# PDB_Schematic_v1_0.net
KiCad netlist of a schematic drawn in Altium Designer
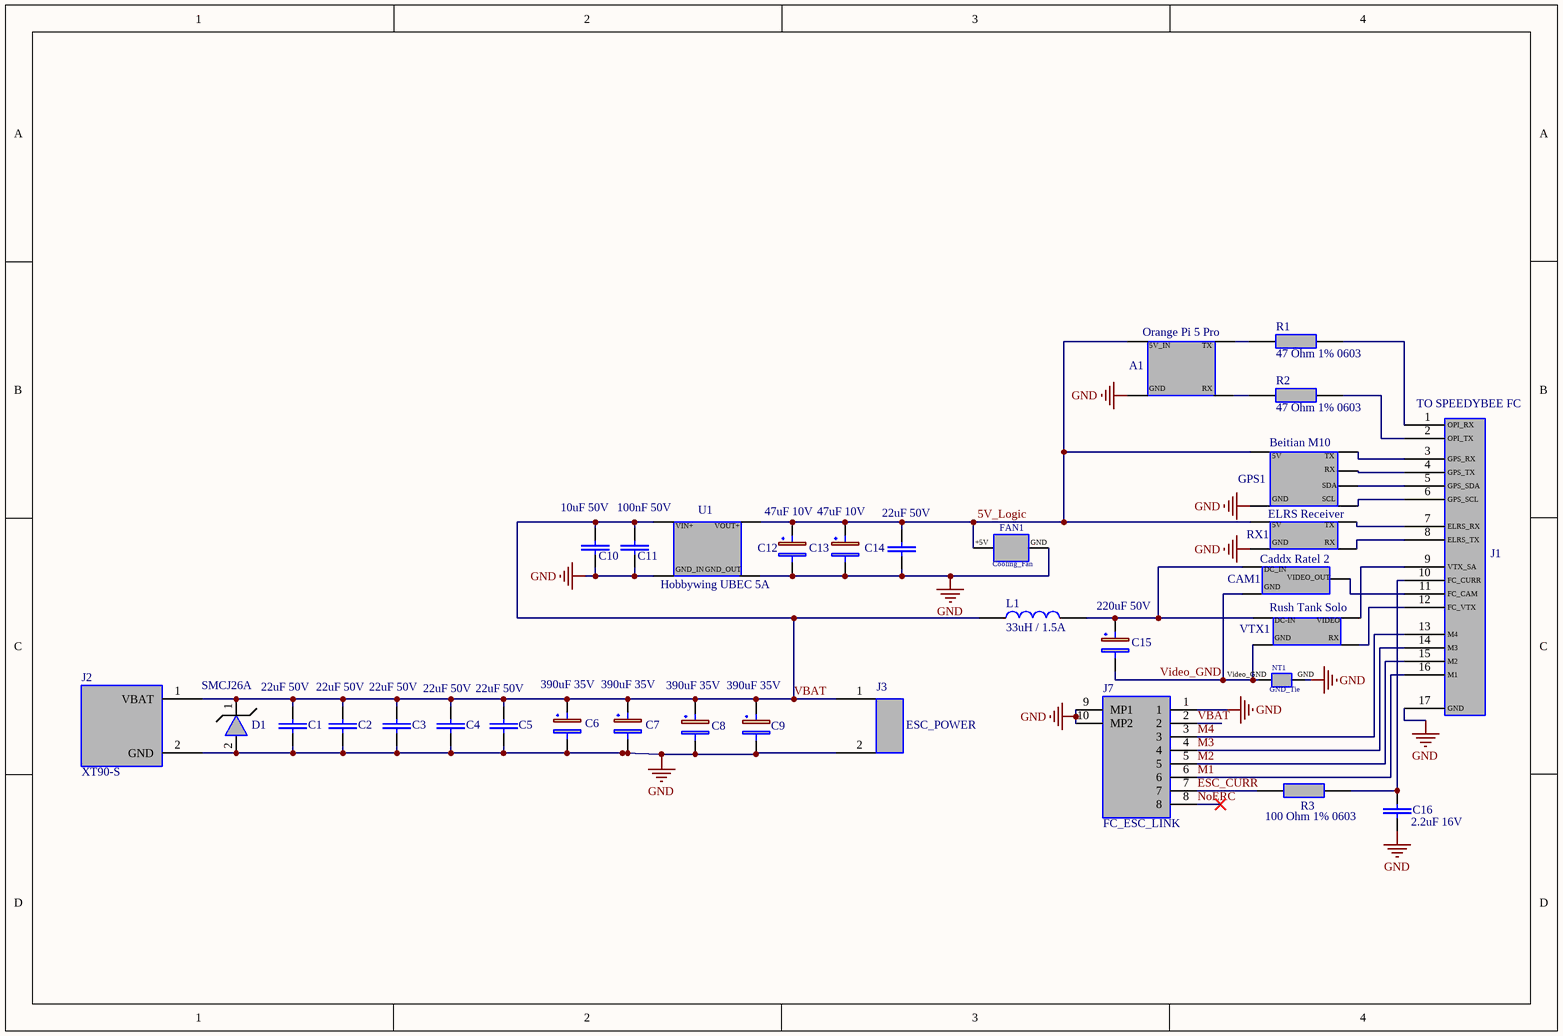
[diagram p0: PDB_Schematic_v1.0.SchDoc]

(export (version "E")
  (design (tool "Eeschema 10.0.6"))
  (components
    (comp (ref "A1")
      (value "Orange Pi 5 Pro")
      (footprint "PDB_Footprints_v1.0:FOOTPRINT_ORANGE_PI")
      (libsource (lib "PDB_Components_v1.0") (part "Orange Pi 5 Pro"))
    )
    (comp (ref "C1")
      (value "22uF 50V")
      (footprint "PDB_Footprints_v1.0:1210")
      (libsource (lib "PDB_Components_v1.0") (part "Cap_MLCC"))
    )
    (comp (ref "C2")
      (value "22uF 50V")
      (footprint "PDB_Footprints_v1.0:1210")
      (libsource (lib "PDB_Components_v1.0") (part "Cap_MLCC"))
    )
    (comp (ref "C3")
      (value "22uF 50V")
      (footprint "PDB_Footprints_v1.0:1210")
      (libsource (lib "PDB_Components_v1.0") (part "Cap_MLCC"))
    )
    (comp (ref "C4")
      (value "22uF 50V")
      (footprint "PDB_Footprints_v1.0:1210")
      (libsource (lib "PDB_Components_v1.0") (part "Cap_MLCC"))
    )
    (comp (ref "C5")
      (value "22uF 50V")
      (footprint "PDB_Footprints_v1.0:1210")
      (libsource (lib "PDB_Components_v1.0") (part "Cap_MLCC"))
    )
    (comp (ref "C6")
      (value "390uF 35V")
      (footprint "PDB_Footprints_v1.0:CAP_ELEC_D10.0_P5.0")
      (description "Low ESR Aluminum Electrolytic Capacitor, Panasonic FR Series, 390uF 35V, Radial, 5mm Lead Pitc")
      (fields (field (name "VOLTAGE") "35V") (field (name "MANUFACTURER") "Panasonic"))
      (libsource (lib "PDB_Components_v1.0") (part "Cap_Low_ESR"))
    )
    (comp (ref "C7")
      (value "390uF 35V")
      (footprint "PDB_Footprints_v1.0:CAP_ELEC_D10.0_P5.0")
      (description "Low ESR Aluminum Electrolytic Capacitor, Panasonic FR Series, 390uF 35V, Radial, 5mm Lead Pitc")
      (fields (field (name "VOLTAGE") "35V") (field (name "MANUFACTURER") "Panasonic"))
      (libsource (lib "PDB_Components_v1.0") (part "Cap_Low_ESR"))
    )
    (comp (ref "C8")
      (value "390uF 35V")
      (footprint "PDB_Footprints_v1.0:CAP_ELEC_D10.0_P5.0")
      (description "Low ESR Aluminum Electrolytic Capacitor, Panasonic FR Series, 390uF 35V, Radial, 5mm Lead Pitc")
      (fields (field (name "VOLTAGE") "35V") (field (name "MANUFACTURER") "Panasonic"))
      (libsource (lib "PDB_Components_v1.0") (part "Cap_Low_ESR"))
    )
    (comp (ref "C9")
      (value "390uF 35V")
      (footprint "PDB_Footprints_v1.0:CAP_ELEC_D10.0_P5.0")
      (description "Low ESR Aluminum Electrolytic Capacitor, Panasonic FR Series, 390uF 35V, Radial, 5mm Lead Pitc")
      (fields (field (name "VOLTAGE") "35V") (field (name "MANUFACTURER") "Panasonic"))
      (libsource (lib "PDB_Components_v1.0") (part "Cap_Low_ESR"))
    )
    (comp (ref "C10")
      (value "10uF 50V")
      (footprint "PDB_Footprints_v1.0:1206")
      (description "Ceramic Capacitor, 10 uF, 50 V, X7R Dielectric, 1206 SMD, UBEC VIN Buffer")
      (libsource (lib "PDB_Components_v1.0") (part "Cap_Cer_10uF_50V_1206"))
    )
    (comp (ref "C11")
      (value "100nF 50V")
      (footprint "PDB_Footprints_v1.0:0603")
      (description "High-Frequency Ceramic Capacitor, 100 nF, 50 V, X7R Dielectric, 0603 SMD, UBEC VIN Decoupling")
      (libsource (lib "PDB_Components_v1.0") (part "Cap_Cer_100nF_50V_0603"))
    )
    (comp (ref "C12")
      (value "47uF 10V")
      (footprint "PDB_Footprints_v1.0:CAP_TANT_3528")
      (description "Polymer Tantalum Capacitor, 47uF, 10V, ±20%, 35 mOhm ESR, SMD 3528-21 (EIA 1210)")
      (fields (field (name "MPN") "T520B476M010ATE035"))
      (libsource (lib "PDB_Components_v1.0") (part "Cap_Tantal_3528"))
    )
    (comp (ref "C13")
      (value "47uF 10V")
      (footprint "PDB_Footprints_v1.0:CAP_TANT_3528")
      (description "Polymer Tantalum Capacitor, 47uF, 10V, ±20%, 35 mOhm ESR, SMD 3528-21 (EIA 1210)")
      (fields (field (name "MPN") "T520B476M010ATE035"))
      (libsource (lib "PDB_Components_v1.0") (part "Cap_Tantal_3528"))
    )
    (comp (ref "C14")
      (value "22uF 50V")
      (footprint "PDB_Footprints_v1.0:1210")
      (description "Multilayer Ceramic Capacitor (MLCC), 22uF 50V, X7R, 1210 (3225 Metric), High-Frequency ESC Filter")
      (libsource (lib "PDB_Components_v1.0") (part "Cap_MLCC"))
    )
    (comp (ref "C15")
      (value "220uF 50V")
      (footprint "PDB_Footprints_v1.0:CAP_ELEC_D10.0_P5.0")
      (description "Low-ESR Aluminum Electrolytic Capacitor, 220 uF, 50 V, Radial, LC Video Filter")
      (libsource (lib "PDB_Components_v1.0") (part "Cap_Low_ESR_220uF_50V"))
    )
    (comp (ref "C16")
      (value "2.2uF 16V")
      (footprint "PDB_Footprints_v1.0:0603")
      (description "Ceramic Capacitor, 2.2 uF, 16 V, X7R Dielectric, 0603 SMD, ESC Current Sensor Filter")
      (libsource (lib "PDB_Components_v1.0") (part "Cap_Cer_2.2uF_16V_0603"))
    )
    (comp (ref "CAM1")
      (value "Caddx Ratel 2")
      (footprint "FOOTPRINT_Caddx_Ratel_2")
      (description "Analog FPV Micro Camera, 1200TVL, Ultra Low Light Starlight")
      (libsource (lib "PDB_Components_v1.0") (part "Caddx Ratel 2"))
    )
    (comp (ref "D1")
      (value "SMCJ26A")
      (footprint "PDB_Footprints_v1.0:DIODE_SMC")
      (description "Transient Voltage Suppressor (TVS) Diode, Unidirectional, 26V Vrwm, 1500W Peak, DO-214AB (SMC)")
      (libsource (lib "PDB_Components_v1.0") (part "SMCJ26A"))
    )
    (comp (ref "FAN1")
      (value "Cooling_Fan")
      (footprint "PDB_Footprints_v1.0:FOOTPRINT_FAN_5V")
      (description "V DC Micro Cooling Fan, 25x25x10mm Active Cooling")
      (libsource (lib "PDB_Components_v1.0") (part "Cooling Fan 5V"))
    )
    (comp (ref "GPS1")
      (value "Beitian M10")
      (footprint "PDB_Footprints_v1.0:FOOTPRINT_BEITIAN_M10")
      (description "GNSS GPS + Compass Module, M10 Platform, UART & I2C Interface")
      (libsource (lib "PDB_Components_v1.0") (part "Beitian M10"))
    )
    (comp (ref "J1")
      (value "TO SPEEDYBEE FC")
      (footprint "PDB_Footprints_v1.0:SpeedyBee_FC")
      (description "15-Pin Signal Interface Hub for Flight Controller (OPi, GPS, ELRS, VTX, GND)")
      (libsource (lib "PDB_Components_v1.0") (part "SpeedyBee FC Signals"))
    )
    (comp (ref "J2")
      (value "XT90-S")
      (footprint "PDB_Footprints_v1.0:XT90-S_PWR")
      (description "High-Current DC Power Connector with Integrated Anti-Spark Resistance, Amass XT90-S, 90A Peak")
      (libsource (lib "PDB_Components_v1.0") (part "XT90-S"))
    )
    (comp (ref "J3")
      (value "ESC_POWER")
      (footprint "PDB_Footprints_v1.0:PADS_ESC_PWR")
      (description "Wire-to-Board Solder Pads Array, 1x2, 2.54mm Pitch")
      (libsource (lib "PDB_Components_v1.0") (part "PADS_WIRE_1X2"))
    )
    (comp (ref "J7")
      (value "FC_ESC_LINK")
      (footprint "PDB_Footprints_v1.0:CONN_JST_SH_BM08B-SRSS-TB_8P")
      (libsource (lib "PDB_Components_v1.0") (part "JST-SH 8-pin"))
    )
    (comp (ref "L1")
      (value "33uH / 1.5A")
      (footprint "PDB_Footprints_v1.0:FOOTPRINT_INDUCTOR_SRN6045")
      (description "Semi-Shielded Power Inductor, Bourns SRN6045 Series, 33uH 2.5A, 0.15 Ohm DCR, LC Video Filter")
      (fields (field (name "MANUFACTURER") "Bourns") (field (name "MANUFACTURER PART NUMBER") "SRN6045-330M"))
      (libsource (lib "PDB_Components_v1.0") (part "Inductor_SMD"))
    )
    (comp (ref "NT1")
      (value "GND_Tie")
      (footprint "PDB_Footprints_v1.0:NET_TIE_0.2MM")
      (description "Net-Tie zero-ohm bridge for ground separation")
      (libsource (lib "PDB_Components_v1.0") (part "NET_TIE"))
    )
    (comp (ref "R1")
      (value "47 Ohm 1% 0603")
      (footprint "PDB_Footprints_v1.0:0603")
      (fields (field (name "PART NUMBER") "RC0603FR-0747RL") (field (name "MANUFACTURER") "Yageo"))
      (libsource (lib "PDB_Components_v1.0") (part "Res_SMD"))
    )
    (comp (ref "R2")
      (value "47 Ohm 1% 0603")
      (footprint "PDB_Footprints_v1.0:0603")
      (fields (field (name "PART NUMBER") "RC0603FR-0747RL") (field (name "MANUFACTURER") "Yageo"))
      (libsource (lib "PDB_Components_v1.0") (part "Res_SMD"))
    )
    (comp (ref "R3")
      (value "100 Ohm 1% 0603")
      (footprint "PDB_Footprints_v1.0:0603")
      (description "Resistor, 100 Ohm, 1%, 1/10W, 0603 SMD, ESC Current Sensor Filter")
      (libsource (lib "PDB_Components_v1.0") (part "Res_100Ohm_0603"))
    )
    (comp (ref "RX1")
      (value "ELRS Receiver")
      (footprint "PDB_Footprints_v1.0:FOOTPRINT_ELRS_RX")
      (description "ExpressLRS 2.4GHz True Diversity Radio Receiver Module")
      (libsource (lib "PDB_Components_v1.0") (part "ExpressLRS RX"))
    )
    (comp (ref "U1")
      (value "Hobbywing UBEC 5A")
      (footprint "PDB_Footprints_v1.0:UBEC_Hobbywing_5A")
      (fields (field (name "MANUFACTURER") "Hobbywing") (field (name "PART NUMBER") "HW30607000"))
      (libsource (lib "PDB_Components_v1.0") (part "UBEC_Hobbywing_5A"))
    )
    (comp (ref "VTX1")
      (value "Rush Tank Solo")
      (footprint "PDB_Footprints_v1.0:FOOTPRINT_VTX_RUSH_SOLO")
      (description "5.8GHz VTX 1.6W Video Transmitter Module")
      (libsource (lib "PDB_Components_v1.0") (part "Rush Tank Solo 1.6W"))
    )
  )
  (nets
    (net (code "1") (name "/5V_Logic") (class "Default")
      (node (ref "A1") (pin "1") (pinfunction "5V_IN_1") (pintype "power_in"))
      (node (ref "C12") (pin "1") (pinfunction "+_1") (pintype "passive"))
      (node (ref "C13") (pin "1") (pinfunction "+_1") (pintype "passive"))
      (node (ref "C14") (pin "2") (pinfunction "-_2") (pintype "passive"))
      (node (ref "FAN1") (pin "1") (pinfunction "+5V_1") (pintype "power_in"))
      (node (ref "GPS1") (pin "1") (pinfunction "5V_1") (pintype "power_in"))
      (node (ref "RX1") (pin "1") (pinfunction "5V_1") (pintype "power_in"))
      (node (ref "U1") (pin "3") (pinfunction "+5.1V_3") (pintype "power_in"))
    )
    (net (code "3") (name "/ESC_CURR") (class "Default")
      (node (ref "J7") (pin "7") (pinfunction "7_7") (pintype "passive"))
      (node (ref "R3") (pin "1") (pinfunction "1_1") (pintype "passive"))
    )
    (net (code "4") (name "/M1") (class "Default")
      (node (ref "J1") (pin "16") (pinfunction "M1_16") (pintype "power_in"))
      (node (ref "J7") (pin "6") (pinfunction "6_6") (pintype "passive"))
    )
    (net (code "5") (name "/M2") (class "Default")
      (node (ref "J1") (pin "15") (pinfunction "M2_15") (pintype "power_in"))
      (node (ref "J7") (pin "5") (pinfunction "5_5") (pintype "passive"))
    )
    (net (code "6") (name "/M3") (class "Default")
      (node (ref "J1") (pin "14") (pinfunction "M3_14") (pintype "power_in"))
      (node (ref "J7") (pin "4") (pinfunction "4_4") (pintype "passive"))
    )
    (net (code "7") (name "/M4") (class "Default")
      (node (ref "J1") (pin "13") (pinfunction "M4_13") (pintype "power_in"))
      (node (ref "J7") (pin "3") (pinfunction "3_3") (pintype "passive"))
    )
    (net (code "8") (name "/NoERC") (class "Default")
      (node (ref "J7") (pin "8") (pinfunction "8_8") (pintype "passive+no_connect"))
    )
    (net (code "9") (name "/VBAT") (class "Default")
      (node (ref "C1") (pin "2") (pinfunction "-_2") (pintype "passive"))
      (node (ref "C10") (pin "2") (pinfunction "-_2") (pintype "passive"))
      (node (ref "C11") (pin "2") (pinfunction "-_2") (pintype "passive"))
      (node (ref "C2") (pin "2") (pinfunction "-_2") (pintype "passive"))
      (node (ref "C3") (pin "2") (pinfunction "-_2") (pintype "passive"))
      (node (ref "C4") (pin "2") (pinfunction "-_2") (pintype "passive"))
      (node (ref "C5") (pin "2") (pinfunction "-_2") (pintype "passive"))
      (node (ref "C6") (pin "1") (pinfunction "+_1") (pintype "passive"))
      (node (ref "C7") (pin "1") (pinfunction "+_1") (pintype "passive"))
      (node (ref "C8") (pin "1") (pinfunction "+_1") (pintype "passive"))
      (node (ref "C9") (pin "1") (pinfunction "+_1") (pintype "passive"))
      (node (ref "D1") (pin "1") (pinfunction "k_1") (pintype "power_in"))
      (node (ref "J2") (pin "1") (pinfunction "VBAT_1") (pintype "power_in"))
      (node (ref "J3") (pin "1") (pintype "passive"))
      (node (ref "J7") (pin "2") (pinfunction "2_2") (pintype "passive"))
      (node (ref "L1") (pin "1") (pinfunction "1_1") (pintype "passive"))
      (node (ref "U1") (pin "1") (pinfunction "VIN+_1") (pintype "power_in"))
    )
    (net (code "10") (name "/Video_GND") (class "Default")
      (node (ref "C15") (pin "2") (pinfunction "-_2") (pintype "passive"))
      (node (ref "CAM1") (pin "2") (pinfunction "GND_2") (pintype "power_in"))
      (node (ref "NT1") (pin "Video_GND") (pinfunction "Video_GND_Video_GND") (pintype "power_in"))
      (node (ref "VTX1") (pin "2") (pinfunction "GND_2") (pintype "power_in"))
    )
    (net (code "11") (name "GND") (class "Default")
      (node (ref "A1") (pin "2") (pinfunction "GND_2") (pintype "power_in"))
      (node (ref "C1") (pin "1") (pinfunction "+_1") (pintype "passive"))
      (node (ref "C10") (pin "1") (pinfunction "+_1") (pintype "passive"))
      (node (ref "C11") (pin "1") (pinfunction "+_1") (pintype "passive"))
      (node (ref "C12") (pin "2") (pinfunction "-_2") (pintype "passive"))
      (node (ref "C13") (pin "2") (pinfunction "-_2") (pintype "passive"))
      (node (ref "C14") (pin "1") (pinfunction "+_1") (pintype "passive"))
      (node (ref "C16") (pin "1") (pinfunction "+_1") (pintype "passive"))
      (node (ref "C2") (pin "1") (pinfunction "+_1") (pintype "passive"))
      (node (ref "C3") (pin "1") (pinfunction "+_1") (pintype "passive"))
      (node (ref "C4") (pin "1") (pinfunction "+_1") (pintype "passive"))
      (node (ref "C5") (pin "1") (pinfunction "+_1") (pintype "passive"))
      (node (ref "C6") (pin "2") (pinfunction "-_2") (pintype "passive"))
      (node (ref "C7") (pin "2") (pinfunction "-_2") (pintype "passive"))
      (node (ref "C8") (pin "2") (pinfunction "-_2") (pintype "passive"))
      (node (ref "C9") (pin "2") (pinfunction "-_2") (pintype "passive"))
      (node (ref "D1") (pin "2") (pinfunction "A_2") (pintype "power_in"))
      (node (ref "FAN1") (pin "2") (pinfunction "GND_2") (pintype "passive"))
      (node (ref "GPS1") (pin "2") (pinfunction "GND_2") (pintype "power_in"))
      (node (ref "J1") (pin "17") (pinfunction "GND_17") (pintype "power_in"))
      (node (ref "J2") (pin "2") (pinfunction "GND_2") (pintype "power_in"))
      (node (ref "J3") (pin "2") (pintype "passive"))
      (node (ref "J7") (pin "1") (pinfunction "1_1") (pintype "passive"))
      (node (ref "J7") (pin "10") (pinfunction "MP2_10") (pintype "passive"))
      (node (ref "J7") (pin "9") (pinfunction "MP1_9") (pintype "passive"))
      (node (ref "NT1") (pin "GND") (pinfunction "20_GND") (pintype "power_in"))
      (node (ref "RX1") (pin "2") (pinfunction "GND_2") (pintype "power_in"))
      (node (ref "U1") (pin "2") (pinfunction "GND_IN_2") (pintype "power_in"))
      (node (ref "U1") (pin "4") (pinfunction "GND_OUT_4") (pintype "power_in"))
    )
    (net (code "12") (name "Net-(A1-+5.1V)") (class "Default")
      (node (ref "A1") (pin "3") (pinfunction "+5.1V_3") (pintype "passive"))
      (node (ref "R1") (pin "1") (pinfunction "1_1") (pintype "passive"))
    )
    (net (code "13") (name "Net-(A1-RX)") (class "Default")
      (node (ref "A1") (pin "4") (pinfunction "RX_4") (pintype "passive"))
      (node (ref "R2") (pin "1") (pinfunction "1_1") (pintype "passive"))
    )
    (net (code "14") (name "Net-(C15-+)") (class "Default")
      (node (ref "C15") (pin "1") (pinfunction "+_1") (pintype "passive"))
      (node (ref "CAM1") (pin "1") (pinfunction "DC_IN_1") (pintype "power_in"))
      (node (ref "L1") (pin "2") (pinfunction "2_2") (pintype "passive"))
      (node (ref "VTX1") (pin "1") (pinfunction "(7-36V)_1") (pintype "power_in"))
    )
    (net (code "15") (name "Net-(C16--)") (class "Default")
      (node (ref "C16") (pin "2") (pinfunction "-_2") (pintype "passive"))
      (node (ref "J1") (pin "10") (pinfunction "FC_CURR_10") (pintype "power_in"))
      (node (ref "R3") (pin "2") (pinfunction "2_2") (pintype "passive"))
    )
    (net (code "16") (name "Net-(CAM1-VIDEO_OUT)") (class "Default")
      (node (ref "CAM1") (pin "3") (pinfunction "VIDEO_OUT_3") (pintype "passive"))
      (node (ref "J1") (pin "11") (pinfunction "FC_CAM_11") (pintype "power_in"))
    )
    (net (code "17") (name "Net-(GPS1-RX)") (class "Default")
      (node (ref "GPS1") (pin "4") (pinfunction "RX_4") (pintype "passive"))
      (node (ref "J1") (pin "4") (pinfunction "GPS_TX_4") (pintype "power_in"))
    )
    (net (code "18") (name "Net-(GPS1-SCL)") (class "Default")
      (node (ref "GPS1") (pin "6") (pinfunction "SCL_6") (pintype "passive"))
      (node (ref "J1") (pin "6") (pinfunction "GPS_SCL_6") (pintype "power_in"))
    )
    (net (code "19") (name "Net-(GPS1-SDA)") (class "Default")
      (node (ref "GPS1") (pin "5") (pinfunction "SDA_5") (pintype "passive"))
      (node (ref "J1") (pin "5") (pinfunction "GPS_SDA_5") (pintype "power_in"))
    )
    (net (code "20") (name "Net-(GPS1-TX)") (class "Default")
      (node (ref "GPS1") (pin "3") (pinfunction "TX_3") (pintype "passive"))
      (node (ref "J1") (pin "3") (pinfunction "GPS_RX_3") (pintype "power_in"))
    )
    (net (code "21") (name "Net-(J1-ELRS_RX)") (class "Default")
      (node (ref "J1") (pin "7") (pinfunction "ELRS_RX_7") (pintype "power_in"))
      (node (ref "RX1") (pin "3") (pinfunction "TX_3") (pintype "passive"))
    )
    (net (code "22") (name "Net-(J1-ELRS_TX)") (class "Default")
      (node (ref "J1") (pin "8") (pinfunction "ELRS_TX_8") (pintype "power_in"))
      (node (ref "RX1") (pin "4") (pinfunction "RX_4") (pintype "passive"))
    )
    (net (code "23") (name "Net-(J1-FC_VTX)") (class "Default")
      (node (ref "J1") (pin "12") (pinfunction "FC_VTX_12") (pintype "power_in"))
      (node (ref "VTX1") (pin "4") (pinfunction "RX_4") (pintype "passive"))
    )
    (net (code "24") (name "Net-(J1-OPI_RX)") (class "Default")
      (node (ref "J1") (pin "1") (pinfunction "OPI_RX_1") (pintype "power_in"))
      (node (ref "R1") (pin "2") (pinfunction "2_2") (pintype "passive"))
    )
    (net (code "25") (name "Net-(J1-OPI_TX)") (class "Default")
      (node (ref "J1") (pin "2") (pinfunction "OPI_TX_2") (pintype "power_in"))
      (node (ref "R2") (pin "2") (pinfunction "2_2") (pintype "passive"))
    )
    (net (code "26") (name "Net-(J1-VTX_SA)") (class "Default")
      (node (ref "J1") (pin "9") (pinfunction "VTX_SA_9") (pintype "power_in"))
      (node (ref "VTX1") (pin "3") (pinfunction "+5.1V_3") (pintype "passive"))
    )
  )
)
